# CircuitoControle.net
KiCad netlist of a schematic drawn in EAGLE
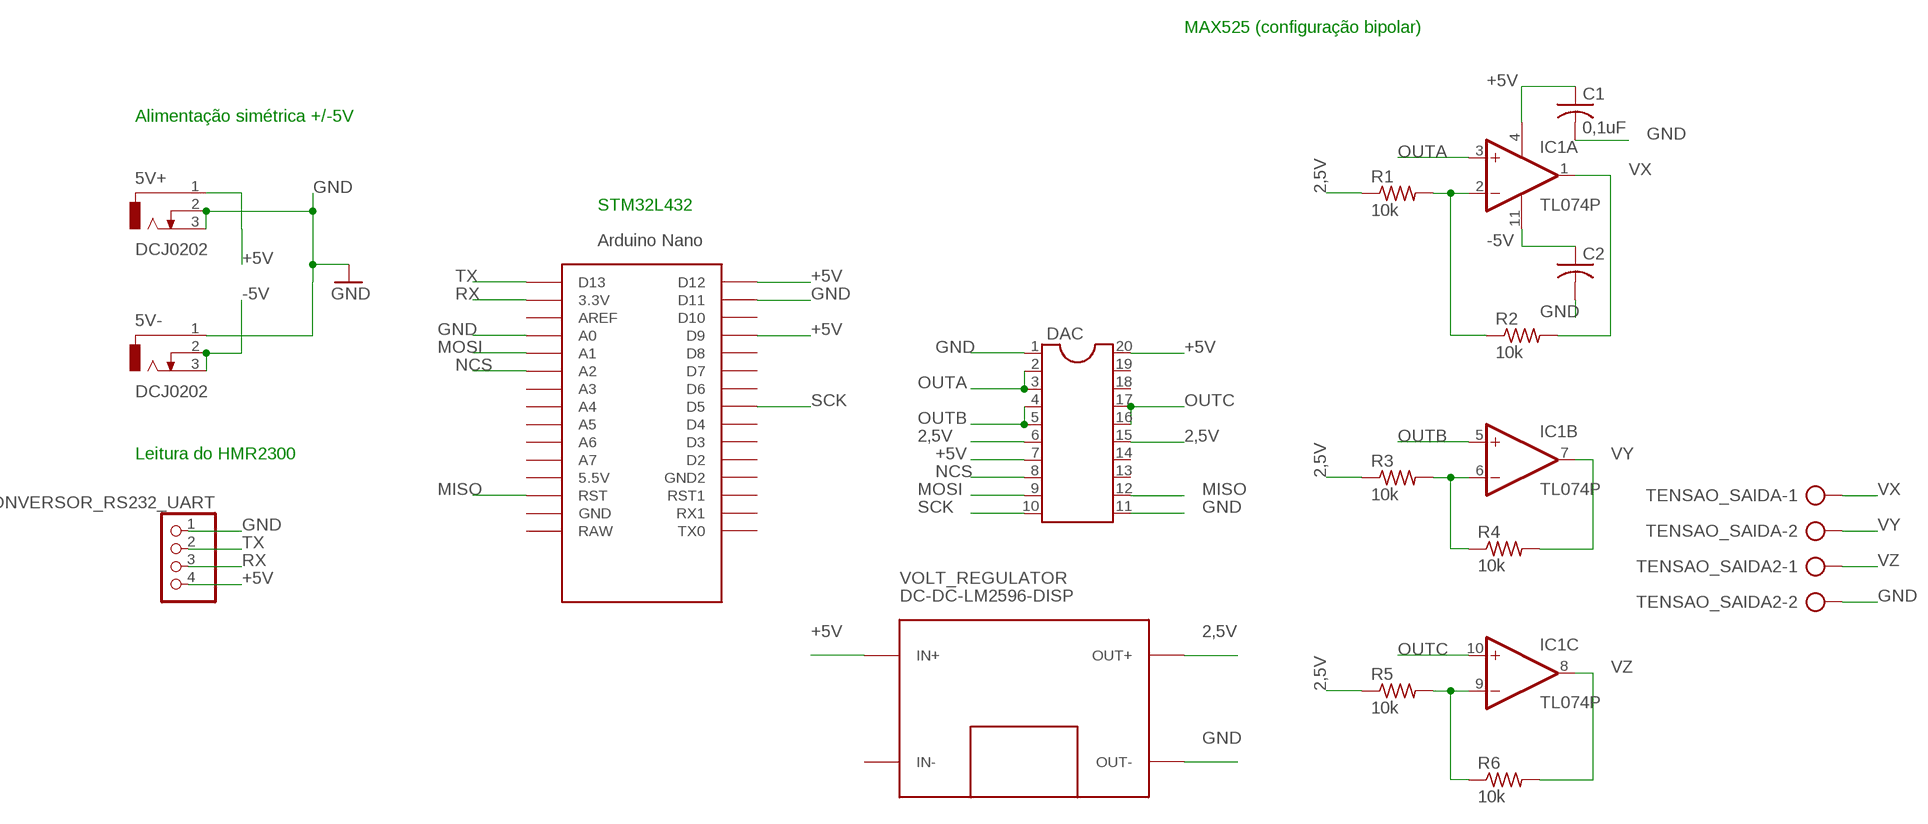
[diagram p0: schematic, sheet 1]

(export (version "E")
  (design (tool "Eeschema 10.0.6"))
  (components
    (comp (ref "5V+")
      (value "DCJ0202")
      (footprint "eagle-import:DCJ0202")
      (libsource (lib "eagle-import") (part "DCJ0202"))
    )
    (comp (ref "5V-")
      (value "DCJ0202")
      (footprint "eagle-import:DCJ0202")
      (libsource (lib "eagle-import") (part "DCJ0202"))
    )
    (comp (ref "C1")
      (value "0,1uF")
      (footprint "eagle-import:C025-024X044")
      (libsource (lib "eagle-import") (part "C-US025-024X044"))
    )
    (comp (ref "C2")
      (value "C-US025-024X044")
      (footprint "eagle-import:C025-024X044")
      (libsource (lib "eagle-import") (part "C-US025-024X044"))
    )
    (comp (ref "CONVERSOR_RS232_UART")
      (value "PINHD-1X4")
      (footprint "eagle-import:1X04")
      (libsource (lib "eagle-import") (part "PINHD-1X4"))
    )
    (comp (ref "DAC")
      (value "DIL20")
      (footprint "eagle-import:DIL20")
      (libsource (lib "eagle-import") (part "DIL20"))
    )
    (comp (ref "IC1")
      (value "TL074P")
      (footprint "eagle-import:DIL14")
      (libsource (lib "eagle-import") (part "TL074P"))
    )
    (comp (ref "R1")
      (value "10k")
      (footprint "eagle-import:0204_5")
      (libsource (lib "eagle-import") (part "R-US_0204/5"))
    )
    (comp (ref "R2")
      (value "10k")
      (footprint "eagle-import:0204_5")
      (libsource (lib "eagle-import") (part "R-US_0204/5"))
    )
    (comp (ref "R3")
      (value "10k")
      (footprint "eagle-import:0204_5")
      (libsource (lib "eagle-import") (part "R-US_0204/5"))
    )
    (comp (ref "R4")
      (value "10k")
      (footprint "eagle-import:0204_5")
      (libsource (lib "eagle-import") (part "R-US_0204/5"))
    )
    (comp (ref "R5")
      (value "10k")
      (footprint "eagle-import:0204_5")
      (libsource (lib "eagle-import") (part "R-US_0204/5"))
    )
    (comp (ref "R6")
      (value "10k")
      (footprint "eagle-import:0204_5")
      (libsource (lib "eagle-import") (part "R-US_0204/5"))
    )
    (comp (ref "STM32")
      (value "NANO")
      (footprint "eagle-import:NANO")
      (libsource (lib "eagle-import") (part "NANO"))
    )
    (comp (ref "TENSAO_SAIDA")
      (value "AK500/2-H")
      (footprint "eagle-import:AK500_2-H")
      (libsource (lib "eagle-import") (part "AK500/2-H"))
    )
    (comp (ref "TENSAO_SAIDA2")
      (value "AK500/2-H")
      (footprint "eagle-import:AK500_2-H")
      (libsource (lib "eagle-import") (part "AK500/2-H"))
    )
    (comp (ref "VOLT_REGULATOR")
      (value "DC-DC-LM2596-DISP")
      (footprint "eagle-import:DC-DC-LM2596-DISP")
      (libsource (lib "eagle-import") (part "DC-DC-LM2596-DISP"))
    )
  )
  (nets
    (net (code "1") (name "/+5V") (class "Default")
      (node (ref "5V+") (pin "1") (pinfunction "1_1") (pintype "passive"))
      (node (ref "C1") (pin "1") (pinfunction "1_1") (pintype "passive"))
      (node (ref "CONVERSOR_RS232_UART") (pin "4") (pinfunction "4_4") (pintype "passive"))
      (node (ref "DAC") (pin "20") (pinfunction "20_20") (pintype "passive"))
      (node (ref "DAC") (pin "7") (pinfunction "7_7") (pintype "passive"))
      (node (ref "IC1") (pin "4") (pinfunction "V+_4") (pintype "power_in"))
      (node (ref "STM32") (pin "D12") (pinfunction "D12_D12") (pintype "bidirectional"))
      (node (ref "STM32") (pin "D9") (pinfunction "D9_D9") (pintype "bidirectional"))
      (node (ref "VOLT_REGULATOR") (pin "IN+") (pinfunction "IN+_IN+") (pintype "bidirectional"))
    )
    (net (code "2") (name "/-5V") (class "Default")
      (node (ref "5V-") (pin "2") (pinfunction "2_2") (pintype "passive"))
      (node (ref "5V-") (pin "3") (pinfunction "3_3") (pintype "passive"))
      (node (ref "C2") (pin "1") (pinfunction "1_1") (pintype "passive"))
      (node (ref "IC1") (pin "11") (pinfunction "V-_11") (pintype "power_in"))
    )
    (net (code "3") (name "/2,5V") (class "Default")
      (node (ref "DAC") (pin "15") (pinfunction "15_15") (pintype "passive"))
      (node (ref "DAC") (pin "6") (pinfunction "6_6") (pintype "passive"))
      (node (ref "R1") (pin "1") (pinfunction "1_1") (pintype "passive"))
      (node (ref "R3") (pin "1") (pinfunction "1_1") (pintype "passive"))
      (node (ref "R5") (pin "1") (pinfunction "1_1") (pintype "passive"))
      (node (ref "VOLT_REGULATOR") (pin "OUT+") (pinfunction "OUT+_OUT+") (pintype "bidirectional"))
    )
    (net (code "4") (name "/MISO") (class "Default")
      (node (ref "DAC") (pin "12") (pinfunction "12_12") (pintype "passive"))
      (node (ref "STM32") (pin "RST") (pinfunction "RST_RST") (pintype "bidirectional"))
    )
    (net (code "5") (name "/MOSI") (class "Default")
      (node (ref "DAC") (pin "9") (pinfunction "9_9") (pintype "passive"))
      (node (ref "STM32") (pin "A1") (pinfunction "A1_A1") (pintype "bidirectional"))
    )
    (net (code "6") (name "/NCS") (class "Default")
      (node (ref "DAC") (pin "8") (pinfunction "8_8") (pintype "passive"))
      (node (ref "STM32") (pin "A2") (pinfunction "A2_A2") (pintype "bidirectional"))
    )
    (net (code "7") (name "/OUTA") (class "Default")
      (node (ref "DAC") (pin "2") (pinfunction "2_2") (pintype "passive"))
      (node (ref "DAC") (pin "3") (pinfunction "3_3") (pintype "passive"))
      (node (ref "IC1") (pin "3") (pinfunction "+IN_3") (pintype "input"))
    )
    (net (code "8") (name "/OUTB") (class "Default")
      (node (ref "DAC") (pin "4") (pinfunction "4_4") (pintype "passive"))
      (node (ref "DAC") (pin "5") (pinfunction "5_5") (pintype "passive"))
      (node (ref "IC1") (pin "5") (pinfunction "+IN_5") (pintype "input"))
    )
    (net (code "9") (name "/OUTC") (class "Default")
      (node (ref "DAC") (pin "16") (pinfunction "16_16") (pintype "passive"))
      (node (ref "DAC") (pin "17") (pinfunction "17_17") (pintype "passive"))
      (node (ref "IC1") (pin "10") (pinfunction "+IN_10") (pintype "input"))
    )
    (net (code "10") (name "/RX") (class "Default")
      (node (ref "CONVERSOR_RS232_UART") (pin "3") (pinfunction "3_3") (pintype "passive"))
      (node (ref "STM32") (pin "3.3V") (pinfunction "3.3V_3.3V") (pintype "bidirectional"))
    )
    (net (code "11") (name "/SCK") (class "Default")
      (node (ref "DAC") (pin "10") (pinfunction "10_10") (pintype "passive"))
      (node (ref "STM32") (pin "D5") (pinfunction "D5_D5") (pintype "bidirectional"))
    )
    (net (code "12") (name "/TX") (class "Default")
      (node (ref "CONVERSOR_RS232_UART") (pin "2") (pinfunction "2_2") (pintype "passive"))
      (node (ref "STM32") (pin "D13") (pinfunction "D13_D13") (pintype "bidirectional"))
    )
    (net (code "13") (name "/VX") (class "Default")
      (node (ref "IC1") (pin "1") (pinfunction "OUT_1") (pintype "output"))
      (node (ref "R2") (pin "2") (pinfunction "2_2") (pintype "passive"))
      (node (ref "TENSAO_SAIDA") (pin "1") (pinfunction "KL_1") (pintype "passive"))
    )
    (net (code "14") (name "/VY") (class "Default")
      (node (ref "IC1") (pin "7") (pinfunction "OUT_7") (pintype "output"))
      (node (ref "R4") (pin "2") (pinfunction "2_2") (pintype "passive"))
      (node (ref "TENSAO_SAIDA") (pin "2") (pinfunction "KL_2") (pintype "passive"))
    )
    (net (code "15") (name "/VZ") (class "Default")
      (node (ref "IC1") (pin "8") (pinfunction "OUT_8") (pintype "output"))
      (node (ref "R6") (pin "2") (pinfunction "2_2") (pintype "passive"))
      (node (ref "TENSAO_SAIDA2") (pin "1") (pinfunction "KL_1") (pintype "passive"))
    )
    (net (code "16") (name "GND") (class "Default")
      (node (ref "5V+") (pin "2") (pinfunction "2_2") (pintype "passive"))
      (node (ref "5V+") (pin "3") (pinfunction "3_3") (pintype "passive"))
      (node (ref "5V-") (pin "1") (pinfunction "1_1") (pintype "passive"))
      (node (ref "C1") (pin "2") (pinfunction "2_2") (pintype "passive"))
      (node (ref "C2") (pin "2") (pinfunction "2_2") (pintype "passive"))
      (node (ref "CONVERSOR_RS232_UART") (pin "1") (pinfunction "1_1") (pintype "passive"))
      (node (ref "DAC") (pin "1") (pinfunction "1_1") (pintype "passive"))
      (node (ref "DAC") (pin "11") (pinfunction "11_11") (pintype "passive"))
      (node (ref "STM32") (pin "A0") (pinfunction "A0_A0") (pintype "bidirectional"))
      (node (ref "STM32") (pin "D11") (pinfunction "D11_D11") (pintype "bidirectional"))
      (node (ref "TENSAO_SAIDA2") (pin "2") (pinfunction "KL_2") (pintype "passive"))
      (node (ref "VOLT_REGULATOR") (pin "OUT-") (pinfunction "OUT-_OUT-") (pintype "bidirectional"))
    )
    (net (code "17") (name "Net-(IC1A--IN)") (class "Default")
      (node (ref "IC1") (pin "2") (pinfunction "-IN_2") (pintype "input"))
      (node (ref "R1") (pin "2") (pinfunction "2_2") (pintype "passive"))
      (node (ref "R2") (pin "1") (pinfunction "1_1") (pintype "passive"))
    )
    (net (code "18") (name "Net-(IC1B--IN)") (class "Default")
      (node (ref "IC1") (pin "6") (pinfunction "-IN_6") (pintype "input"))
      (node (ref "R3") (pin "2") (pinfunction "2_2") (pintype "passive"))
      (node (ref "R4") (pin "1") (pinfunction "1_1") (pintype "passive"))
    )
    (net (code "19") (name "Net-(IC1C--IN)") (class "Default")
      (node (ref "IC1") (pin "9") (pinfunction "-IN_9") (pintype "input"))
      (node (ref "R5") (pin "2") (pinfunction "2_2") (pintype "passive"))
      (node (ref "R6") (pin "1") (pinfunction "1_1") (pintype "passive"))
    )
    (net (code "20") (name "unconnected-(DAC-Pad13)") (class "Default")
      (node (ref "DAC") (pin "13") (pinfunction "13_13") (pintype "passive"))
    )
    (net (code "21") (name "unconnected-(DAC-Pad14)") (class "Default")
      (node (ref "DAC") (pin "14") (pinfunction "14_14") (pintype "passive"))
    )
    (net (code "22") (name "unconnected-(DAC-Pad18)") (class "Default")
      (node (ref "DAC") (pin "18") (pinfunction "18_18") (pintype "passive"))
    )
    (net (code "23") (name "unconnected-(DAC-Pad19)") (class "Default")
      (node (ref "DAC") (pin "19") (pinfunction "19_19") (pintype "passive"))
    )
    (net (code "24") (name "unconnected-(STM32-5.5V-Pad5V)") (class "Default")
      (node (ref "STM32") (pin "5V") (pinfunction "5.5V_5V") (pintype "bidirectional"))
    )
    (net (code "25") (name "unconnected-(STM32-GND2-PadGND1)") (class "Default")
      (node (ref "STM32") (pin "GND1") (pinfunction "GND2_GND1") (pintype "bidirectional"))
    )
    (net (code "26") (name "unconnected-(STM32-PadA3)") (class "Default")
      (node (ref "STM32") (pin "A3") (pinfunction "A3_A3") (pintype "bidirectional"))
    )
    (net (code "27") (name "unconnected-(STM32-PadA4)") (class "Default")
      (node (ref "STM32") (pin "A4") (pinfunction "A4_A4") (pintype "bidirectional"))
    )
    (net (code "28") (name "unconnected-(STM32-PadA5)") (class "Default")
      (node (ref "STM32") (pin "A5") (pinfunction "A5_A5") (pintype "bidirectional"))
    )
    (net (code "29") (name "unconnected-(STM32-PadA6)") (class "Default")
      (node (ref "STM32") (pin "A6") (pinfunction "A6_A6") (pintype "bidirectional"))
    )
    (net (code "30") (name "unconnected-(STM32-PadA7)") (class "Default")
      (node (ref "STM32") (pin "A7") (pinfunction "A7_A7") (pintype "bidirectional"))
    )
    (net (code "31") (name "unconnected-(STM32-PadAREF)") (class "Default")
      (node (ref "STM32") (pin "AREF") (pinfunction "AREF_AREF") (pintype "bidirectional"))
    )
    (net (code "32") (name "unconnected-(STM32-PadD2)") (class "Default")
      (node (ref "STM32") (pin "D2") (pinfunction "D2_D2") (pintype "bidirectional"))
    )
    (net (code "33") (name "unconnected-(STM32-PadD3)") (class "Default")
      (node (ref "STM32") (pin "D3") (pinfunction "D3_D3") (pintype "bidirectional"))
    )
    (net (code "34") (name "unconnected-(STM32-PadD4)") (class "Default")
      (node (ref "STM32") (pin "D4") (pinfunction "D4_D4") (pintype "bidirectional"))
    )
    (net (code "35") (name "unconnected-(STM32-PadD6)") (class "Default")
      (node (ref "STM32") (pin "D6") (pinfunction "D6_D6") (pintype "bidirectional"))
    )
    (net (code "36") (name "unconnected-(STM32-PadD7)") (class "Default")
      (node (ref "STM32") (pin "D7") (pinfunction "D7_D7") (pintype "bidirectional"))
    )
    (net (code "37") (name "unconnected-(STM32-PadD8)") (class "Default")
      (node (ref "STM32") (pin "D8") (pinfunction "D8_D8") (pintype "bidirectional"))
    )
    (net (code "38") (name "unconnected-(STM32-PadD10)") (class "Default")
      (node (ref "STM32") (pin "D10") (pinfunction "D10_D10") (pintype "bidirectional"))
    )
    (net (code "39") (name "unconnected-(STM32-PadGND)") (class "Default")
      (node (ref "STM32") (pin "GND") (pinfunction "GND_GND") (pintype "bidirectional"))
    )
    (net (code "40") (name "unconnected-(STM32-PadICSP1)") (class "Default")
      (node (ref "STM32") (pin "ICSP1") (pinfunction "ICSP1_ICSP1") (pintype "bidirectional"))
    )
    (net (code "41") (name "unconnected-(STM32-PadICSP2)") (class "Default")
      (node (ref "STM32") (pin "ICSP2") (pinfunction "ICSP2_ICSP2") (pintype "bidirectional"))
    )
    (net (code "42") (name "unconnected-(STM32-PadICSP3)") (class "Default")
      (node (ref "STM32") (pin "ICSP3") (pinfunction "ICSP3_ICSP3") (pintype "bidirectional"))
    )
    (net (code "43") (name "unconnected-(STM32-PadICSP4)") (class "Default")
      (node (ref "STM32") (pin "ICSP4") (pinfunction "ICSP4_ICSP4") (pintype "bidirectional"))
    )
    (net (code "44") (name "unconnected-(STM32-PadICSP5)") (class "Default")
      (node (ref "STM32") (pin "ICSP5") (pinfunction "ICSP5_ICSP5") (pintype "bidirectional"))
    )
    (net (code "45") (name "unconnected-(STM32-PadICSP6)") (class "Default")
      (node (ref "STM32") (pin "ICSP6") (pinfunction "ICSP6_ICSP6") (pintype "bidirectional"))
    )
    (net (code "46") (name "unconnected-(STM32-PadRAW)") (class "Default")
      (node (ref "STM32") (pin "RAW") (pinfunction "RAW_RAW") (pintype "bidirectional"))
    )
    (net (code "47") (name "unconnected-(STM32-PadRST1)") (class "Default")
      (node (ref "STM32") (pin "RST1") (pinfunction "RST1_RST1") (pintype "bidirectional"))
    )
    (net (code "48") (name "unconnected-(STM32-PadRX1)") (class "Default")
      (node (ref "STM32") (pin "RX1") (pinfunction "RX1_RX1") (pintype "bidirectional"))
    )
    (net (code "49") (name "unconnected-(STM32-PadTX0)") (class "Default")
      (node (ref "STM32") (pin "TX0") (pinfunction "TX0_TX0") (pintype "bidirectional"))
    )
    (net (code "50") (name "unconnected-(VOLT_REGULATOR-PadIN-)") (class "Default")
      (node (ref "VOLT_REGULATOR") (pin "IN-") (pinfunction "IN-_IN-") (pintype "bidirectional"))
    )
  )
)
